# design.net
KiCad netlist of a schematic drawn in EasyEDA
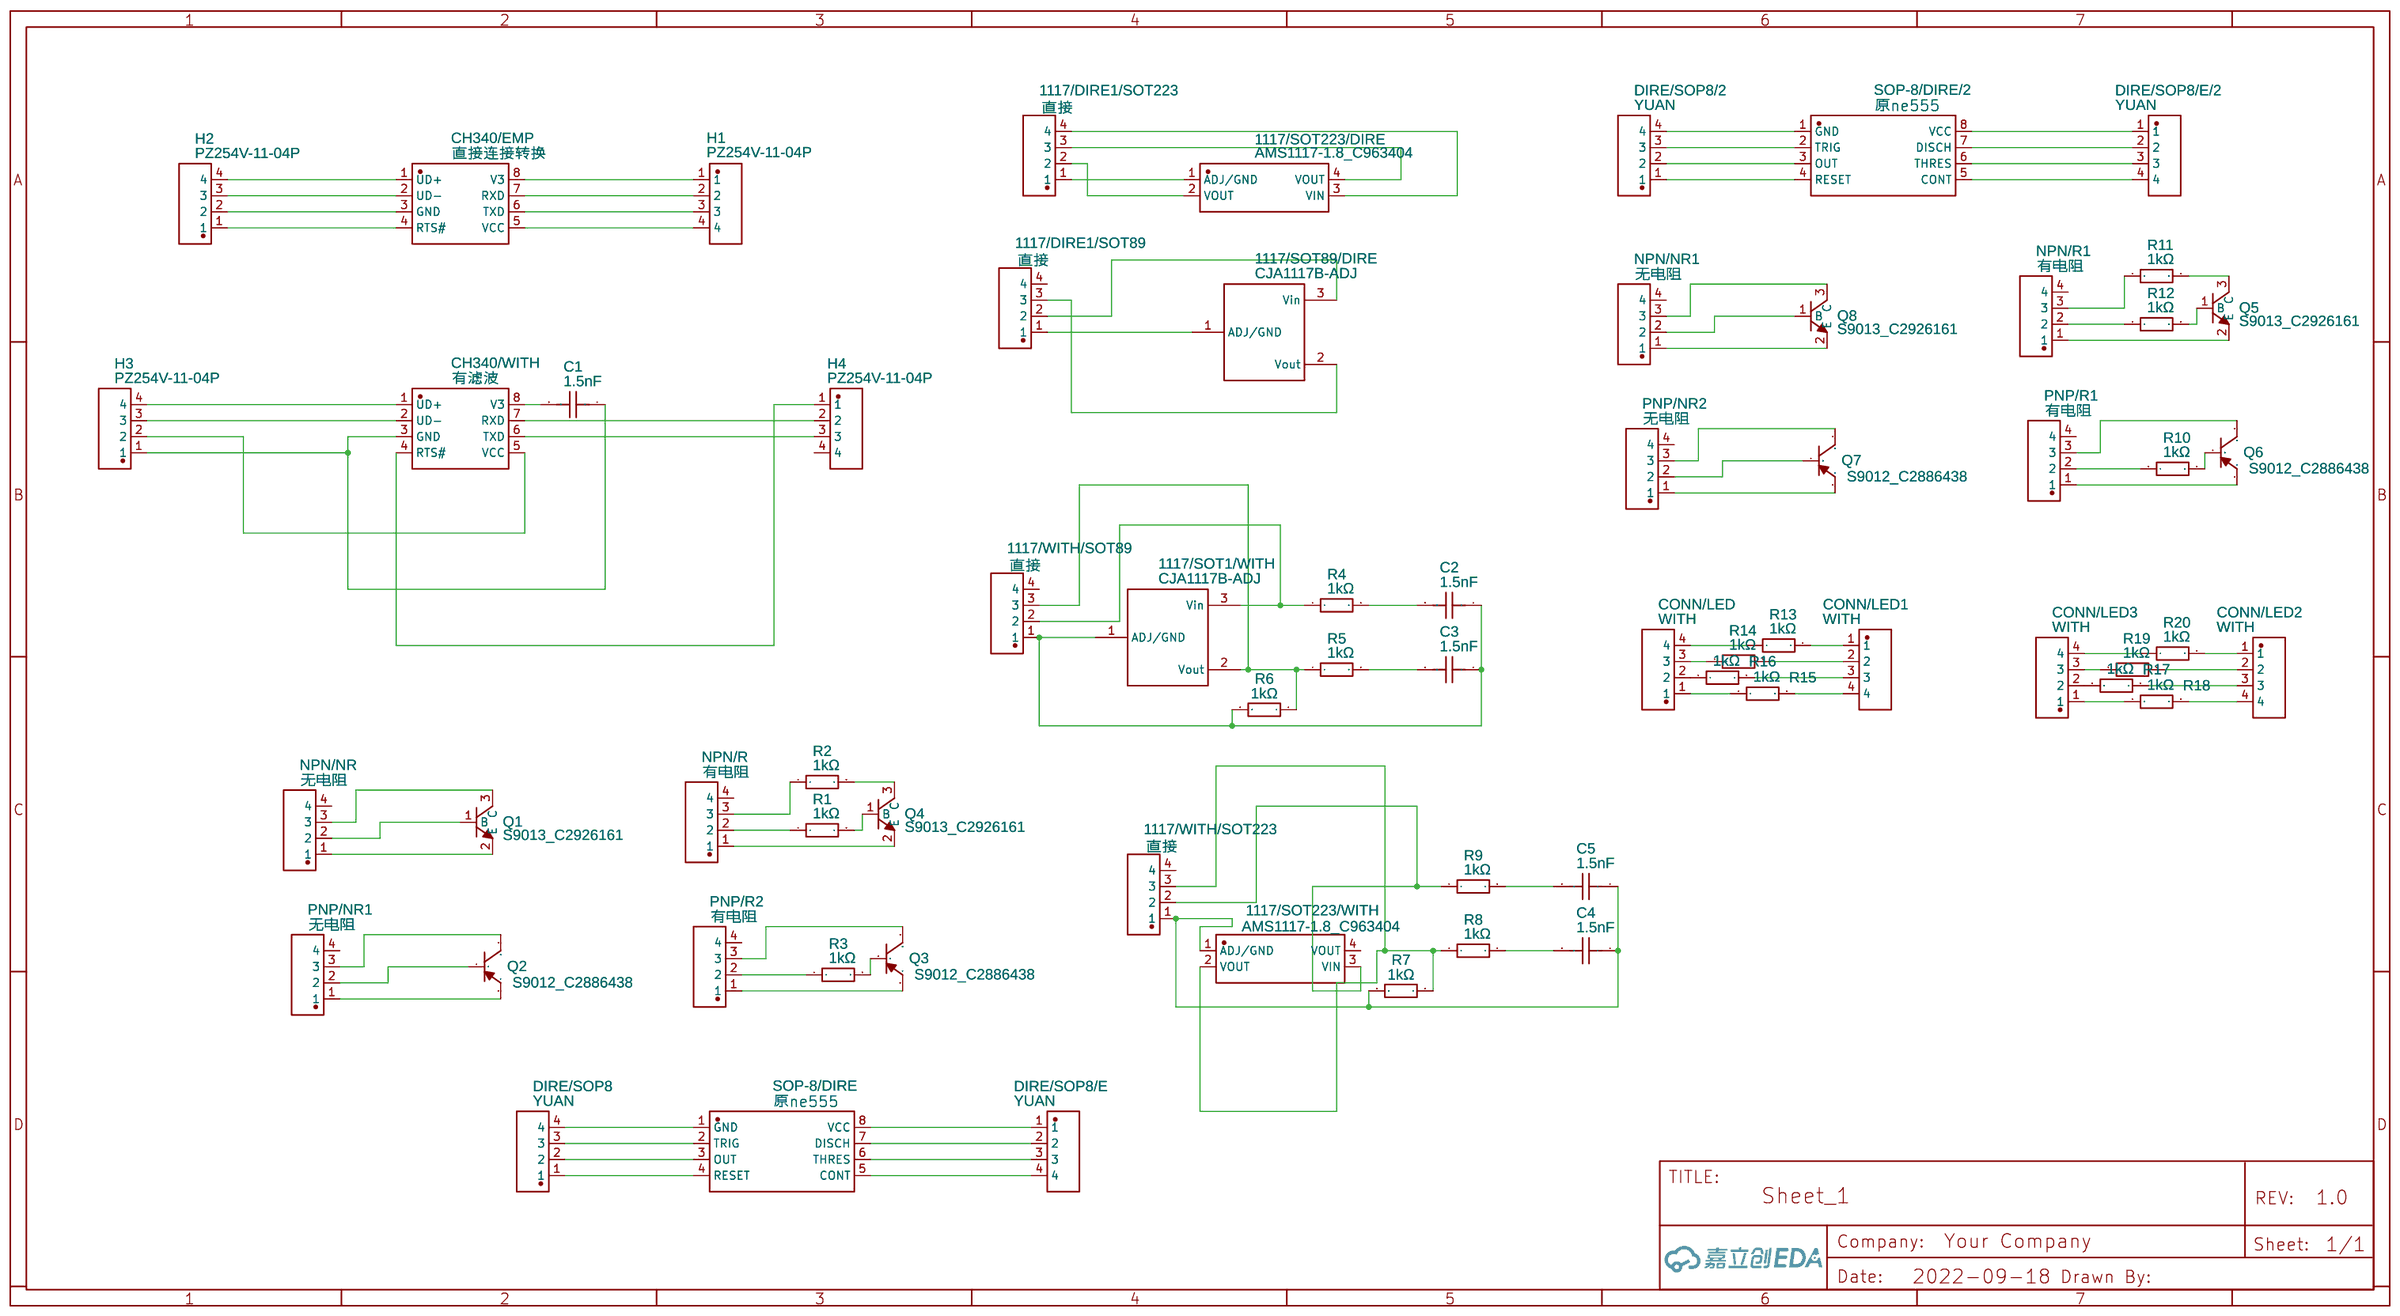
[diagram p0: schematic sheet]

(export (version "E")
  (design (tool "Eeschema 10.0.6"))
  (components
    (comp (ref "1117/DIRE1/SOT89")
      (value "直接")
      (fields
        (field (name "BOM_Manufacturer Part") "PZ254V-11-04P")
        (field (name "BOM_Supplier Part") "C492403")
      )
      (libsource (lib "") (part "PZ254V-11-04P_8"))
    )
    (comp (ref "1117/DIRE1/SOT223")
      (value "直接")
      (fields
        (field (name "BOM_Manufacturer Part") "PZ254V-11-04P")
        (field (name "BOM_Supplier Part") "C492403")
      )
      (libsource (lib "") (part "PZ254V-11-04P_8"))
    )
    (comp (ref "1117/SOT1/WITH")
      (value "CJA1117B-ADJ")
      (fields (field (name "BOM_Supplier Part") "C107222"))
      (libsource (lib "") (part "CJA1117B-ADJ"))
    )
    (comp (ref "1117/SOT89/DIRE")
      (value "CJA1117B-ADJ")
      (fields (field (name "BOM_Supplier Part") "C107222"))
      (libsource (lib "") (part "CJA1117B-ADJ_1"))
    )
    (comp (ref "1117/SOT223/DIRE")
      (value "AMS1117-1.8_C963404")
      (fields
        (field (name "BOM_Manufacturer Part") "AMS1117-1.8")
        (field (name "BOM_Supplier Part") "C963404")
      )
      (libsource (lib "") (part "AMS1117-1.8_C963404"))
    )
    (comp (ref "1117/SOT223/WITH")
      (value "AMS1117-1.8_C963404")
      (fields
        (field (name "BOM_Manufacturer Part") "AMS1117-1.8")
        (field (name "BOM_Supplier Part") "C963404")
      )
      (libsource (lib "") (part "AMS1117-1.8_C963404_1"))
    )
    (comp (ref "1117/WITH/SOT89")
      (value "直接")
      (fields
        (field (name "BOM_Manufacturer Part") "PZ254V-11-04P")
        (field (name "BOM_Supplier Part") "C492403")
      )
      (libsource (lib "") (part "PZ254V-11-04P_9"))
    )
    (comp (ref "1117/WITH/SOT223")
      (value "直接")
      (fields
        (field (name "BOM_Manufacturer Part") "PZ254V-11-04P")
        (field (name "BOM_Supplier Part") "C492403")
      )
      (libsource (lib "") (part "PZ254V-11-04P_9"))
    )
    (comp (ref "C1")
      (value "1.5nF")
      (fields
        (field (name "BOM_Manufacturer Part") "CL10B152KB8NNNC")
        (field (name "BOM_Supplier Part") "C37788")
      )
      (libsource (lib "") (part "CL10B152KB8NNNC"))
    )
    (comp (ref "C2")
      (value "1.5nF")
      (fields
        (field (name "BOM_Manufacturer Part") "CL10B152KB8NNNC")
        (field (name "BOM_Supplier Part") "C37788")
      )
      (libsource (lib "") (part "CL10B152KB8NNNC"))
    )
    (comp (ref "C3")
      (value "1.5nF")
      (fields
        (field (name "BOM_Manufacturer Part") "CL10B152KB8NNNC")
        (field (name "BOM_Supplier Part") "C37788")
      )
      (libsource (lib "") (part "CL10B152KB8NNNC"))
    )
    (comp (ref "C4")
      (value "1.5nF")
      (fields
        (field (name "BOM_Manufacturer Part") "CL10B152KB8NNNC")
        (field (name "BOM_Supplier Part") "C37788")
      )
      (libsource (lib "") (part "CL10B152KB8NNNC"))
    )
    (comp (ref "C5")
      (value "1.5nF")
      (fields
        (field (name "BOM_Manufacturer Part") "CL10B152KB8NNNC")
        (field (name "BOM_Supplier Part") "C37788")
      )
      (libsource (lib "") (part "CL10B152KB8NNNC"))
    )
    (comp (ref "CH340/EMP")
      (value "直接连接转换")
      (fields (field (name "BOM_Manufacturer Part") "CH340N") (field (name "BOM_Supplier Part") "C2977777"))
      (libsource (lib "") (part "CH340N_C2977777"))
    )
    (comp (ref "CH340/WITH")
      (value "有滤波")
      (fields (field (name "BOM_Manufacturer Part") "CH340N") (field (name "BOM_Supplier Part") "C2977777"))
      (libsource (lib "") (part "CH340N_C2977777_1"))
    )
    (comp (ref "CONN/LED")
      (value "WITH")
      (fields
        (field (name "BOM_Manufacturer Part") "PZ254V-11-04P")
        (field (name "BOM_Supplier Part") "C492403")
      )
      (libsource (lib "") (part "PZ254V-11-04P_2"))
    )
    (comp (ref "CONN/LED1")
      (value "WITH")
      (fields
        (field (name "BOM_Manufacturer Part") "PZ254V-11-04P")
        (field (name "BOM_Supplier Part") "C492403")
      )
      (libsource (lib "") (part "PZ254V-11-04P"))
    )
    (comp (ref "CONN/LED2")
      (value "WITH")
      (fields
        (field (name "BOM_Manufacturer Part") "PZ254V-11-04P")
        (field (name "BOM_Supplier Part") "C492403")
      )
      (libsource (lib "") (part "PZ254V-11-04P"))
    )
    (comp (ref "CONN/LED3")
      (value "WITH")
      (fields
        (field (name "BOM_Manufacturer Part") "PZ254V-11-04P")
        (field (name "BOM_Supplier Part") "C492403")
      )
      (libsource (lib "") (part "PZ254V-11-04P_2"))
    )
    (comp (ref "DIRE/SOP8")
      (value "YUAN")
      (fields
        (field (name "BOM_Manufacturer Part") "PZ254V-11-04P")
        (field (name "BOM_Supplier Part") "C492403")
      )
      (libsource (lib "") (part "PZ254V-11-04P_1"))
    )
    (comp (ref "DIRE/SOP8/2")
      (value "YUAN")
      (fields
        (field (name "BOM_Manufacturer Part") "PZ254V-11-04P")
        (field (name "BOM_Supplier Part") "C492403")
      )
      (libsource (lib "") (part "PZ254V-11-04P_4"))
    )
    (comp (ref "DIRE/SOP8/E")
      (value "YUAN")
      (fields
        (field (name "BOM_Manufacturer Part") "PZ254V-11-04P")
        (field (name "BOM_Supplier Part") "C492403")
      )
      (libsource (lib "") (part "PZ254V-11-04P_10"))
    )
    (comp (ref "DIRE/SOP8/E/2")
      (value "YUAN")
      (fields
        (field (name "BOM_Manufacturer Part") "PZ254V-11-04P")
        (field (name "BOM_Supplier Part") "C492403")
      )
      (libsource (lib "") (part "PZ254V-11-04P_13"))
    )
    (comp (ref "H1")
      (value "PZ254V-11-04P")
      (fields (field (name "BOM_Supplier Part") "C492403"))
      (libsource (lib "") (part "PZ254V-11-04P_3"))
    )
    (comp (ref "H2")
      (value "PZ254V-11-04P")
      (fields (field (name "BOM_Supplier Part") "C492403"))
      (libsource (lib "") (part "PZ254V-11-04P_12"))
    )
    (comp (ref "H3")
      (value "PZ254V-11-04P")
      (fields (field (name "BOM_Supplier Part") "C492403"))
      (libsource (lib "") (part "PZ254V-11-04P_12"))
    )
    (comp (ref "H4")
      (value "PZ254V-11-04P")
      (fields (field (name "BOM_Supplier Part") "C492403"))
      (libsource (lib "") (part "PZ254V-11-04P_3"))
    )
    (comp (ref "NPN/NR")
      (value "无电阻")
      (fields
        (field (name "BOM_Manufacturer Part") "PZ254V-11-04P")
        (field (name "BOM_Supplier Part") "C492403")
      )
      (libsource (lib "") (part "PZ254V-11-04P_7"))
    )
    (comp (ref "NPN/NR1")
      (value "无电阻")
      (fields
        (field (name "BOM_Manufacturer Part") "PZ254V-11-04P")
        (field (name "BOM_Supplier Part") "C492403")
      )
      (libsource (lib "") (part "PZ254V-11-04P_7"))
    )
    (comp (ref "NPN/R")
      (value "有电阻")
      (fields
        (field (name "BOM_Manufacturer Part") "PZ254V-11-04P")
        (field (name "BOM_Supplier Part") "C492403")
      )
      (libsource (lib "") (part "PZ254V-11-04P_6"))
    )
    (comp (ref "NPN/R1")
      (value "有电阻")
      (fields
        (field (name "BOM_Manufacturer Part") "PZ254V-11-04P")
        (field (name "BOM_Supplier Part") "C492403")
      )
      (libsource (lib "") (part "PZ254V-11-04P_6"))
    )
    (comp (ref "PNP/NR1")
      (value "无电阻")
      (fields
        (field (name "BOM_Manufacturer Part") "PZ254V-11-04P")
        (field (name "BOM_Supplier Part") "C492403")
      )
      (libsource (lib "") (part "PZ254V-11-04P_5"))
    )
    (comp (ref "PNP/NR2")
      (value "无电阻")
      (fields
        (field (name "BOM_Manufacturer Part") "PZ254V-11-04P")
        (field (name "BOM_Supplier Part") "C492403")
      )
      (libsource (lib "") (part "PZ254V-11-04P_5"))
    )
    (comp (ref "PNP/R1")
      (value "有电阻")
      (fields
        (field (name "BOM_Manufacturer Part") "PZ254V-11-04P")
        (field (name "BOM_Supplier Part") "C492403")
      )
      (libsource (lib "") (part "PZ254V-11-04P_11"))
    )
    (comp (ref "PNP/R2")
      (value "有电阻")
      (fields
        (field (name "BOM_Manufacturer Part") "PZ254V-11-04P")
        (field (name "BOM_Supplier Part") "C492403")
      )
      (libsource (lib "") (part "PZ254V-11-04P_11"))
    )
    (comp (ref "Q1")
      (value "S9013_C2926161")
      (fields (field (name "BOM_Manufacturer Part") "S9013") (field (name "BOM_Supplier Part") "C2926161"))
      (libsource (lib "") (part "S9013_C2926161"))
    )
    (comp (ref "Q2")
      (value "S9012_C2886438")
      (fields (field (name "BOM_Manufacturer Part") "S9012") (field (name "BOM_Supplier Part") "C2886438"))
      (libsource (lib "") (part "S9012_C2886438"))
    )
    (comp (ref "Q3")
      (value "S9012_C2886438")
      (fields (field (name "BOM_Manufacturer Part") "S9012") (field (name "BOM_Supplier Part") "C2886438"))
      (libsource (lib "") (part "S9012_C2886438"))
    )
    (comp (ref "Q4")
      (value "S9013_C2926161")
      (fields (field (name "BOM_Manufacturer Part") "S9013") (field (name "BOM_Supplier Part") "C2926161"))
      (libsource (lib "") (part "S9013_C2926161"))
    )
    (comp (ref "Q5")
      (value "S9013_C2926161")
      (fields (field (name "BOM_Manufacturer Part") "S9013") (field (name "BOM_Supplier Part") "C2926161"))
      (libsource (lib "") (part "S9013_C2926161"))
    )
    (comp (ref "Q6")
      (value "S9012_C2886438")
      (fields (field (name "BOM_Manufacturer Part") "S9012") (field (name "BOM_Supplier Part") "C2886438"))
      (libsource (lib "") (part "S9012_C2886438"))
    )
    (comp (ref "Q7")
      (value "S9012_C2886438")
      (fields (field (name "BOM_Manufacturer Part") "S9012") (field (name "BOM_Supplier Part") "C2886438"))
      (libsource (lib "") (part "S9012_C2886438"))
    )
    (comp (ref "Q8")
      (value "S9013_C2926161")
      (fields (field (name "BOM_Manufacturer Part") "S9013") (field (name "BOM_Supplier Part") "C2926161"))
      (libsource (lib "") (part "S9013_C2926161"))
    )
    (comp (ref "R1")
      (value "1kΩ")
      (fields
        (field (name "BOM_Manufacturer Part") "0603WAF1001T5E")
        (field (name "BOM_Supplier Part") "C21190")
      )
      (libsource (lib "") (part "0603WAF1001T5E"))
    )
    (comp (ref "R2")
      (value "1kΩ")
      (fields
        (field (name "BOM_Manufacturer Part") "0603WAF1001T5E")
        (field (name "BOM_Supplier Part") "C21190")
      )
      (libsource (lib "") (part "0603WAF1001T5E"))
    )
    (comp (ref "R3")
      (value "1kΩ")
      (fields
        (field (name "BOM_Manufacturer Part") "0603WAF1001T5E")
        (field (name "BOM_Supplier Part") "C21190")
      )
      (libsource (lib "") (part "0603WAF1001T5E"))
    )
    (comp (ref "R4")
      (value "1kΩ")
      (fields
        (field (name "BOM_Manufacturer Part") "0603WAF1001T5E")
        (field (name "BOM_Supplier Part") "C21190")
      )
      (libsource (lib "") (part "0603WAF1001T5E"))
    )
    (comp (ref "R5")
      (value "1kΩ")
      (fields
        (field (name "BOM_Manufacturer Part") "0603WAF1001T5E")
        (field (name "BOM_Supplier Part") "C21190")
      )
      (libsource (lib "") (part "0603WAF1001T5E"))
    )
    (comp (ref "R6")
      (value "1kΩ")
      (fields
        (field (name "BOM_Manufacturer Part") "0603WAF1001T5E")
        (field (name "BOM_Supplier Part") "C21190")
      )
      (libsource (lib "") (part "0603WAF1001T5E_1"))
    )
    (comp (ref "R7")
      (value "1kΩ")
      (fields
        (field (name "BOM_Manufacturer Part") "0603WAF1001T5E")
        (field (name "BOM_Supplier Part") "C21190")
      )
      (libsource (lib "") (part "0603WAF1001T5E_1"))
    )
    (comp (ref "R8")
      (value "1kΩ")
      (fields
        (field (name "BOM_Manufacturer Part") "0603WAF1001T5E")
        (field (name "BOM_Supplier Part") "C21190")
      )
      (libsource (lib "") (part "0603WAF1001T5E"))
    )
    (comp (ref "R9")
      (value "1kΩ")
      (fields
        (field (name "BOM_Manufacturer Part") "0603WAF1001T5E")
        (field (name "BOM_Supplier Part") "C21190")
      )
      (libsource (lib "") (part "0603WAF1001T5E"))
    )
    (comp (ref "R10")
      (value "1kΩ")
      (fields
        (field (name "BOM_Manufacturer Part") "0603WAF1001T5E")
        (field (name "BOM_Supplier Part") "C21190")
      )
      (libsource (lib "") (part "0603WAF1001T5E"))
    )
    (comp (ref "R11")
      (value "1kΩ")
      (fields
        (field (name "BOM_Manufacturer Part") "0603WAF1001T5E")
        (field (name "BOM_Supplier Part") "C21190")
      )
      (libsource (lib "") (part "0603WAF1001T5E"))
    )
    (comp (ref "R12")
      (value "1kΩ")
      (fields
        (field (name "BOM_Manufacturer Part") "0603WAF1001T5E")
        (field (name "BOM_Supplier Part") "C21190")
      )
      (libsource (lib "") (part "0603WAF1001T5E"))
    )
    (comp (ref "R13")
      (value "1kΩ")
      (fields
        (field (name "BOM_Manufacturer Part") "0603WAF1001T5E")
        (field (name "BOM_Supplier Part") "C21190")
      )
      (libsource (lib "") (part "0603WAF1001T5E"))
    )
    (comp (ref "R14")
      (value "1kΩ")
      (fields
        (field (name "BOM_Manufacturer Part") "0603WAF1001T5E")
        (field (name "BOM_Supplier Part") "C21190")
      )
      (libsource (lib "") (part "0603WAF1001T5E"))
    )
    (comp (ref "R15")
      (value "1kΩ")
      (fields
        (field (name "BOM_Manufacturer Part") "0603WAF1001T5E")
        (field (name "BOM_Supplier Part") "C21190")
      )
      (libsource (lib "") (part "0603WAF1001T5E"))
    )
    (comp (ref "R16")
      (value "1kΩ")
      (fields
        (field (name "BOM_Manufacturer Part") "0603WAF1001T5E")
        (field (name "BOM_Supplier Part") "C21190")
      )
      (libsource (lib "") (part "0603WAF1001T5E"))
    )
    (comp (ref "R17")
      (value "1kΩ")
      (fields
        (field (name "BOM_Manufacturer Part") "0603WAF1001T5E")
        (field (name "BOM_Supplier Part") "C21190")
      )
      (libsource (lib "") (part "0603WAF1001T5E"))
    )
    (comp (ref "R18")
      (value "1kΩ")
      (fields
        (field (name "BOM_Manufacturer Part") "0603WAF1001T5E")
        (field (name "BOM_Supplier Part") "C21190")
      )
      (libsource (lib "") (part "0603WAF1001T5E"))
    )
    (comp (ref "R19")
      (value "1kΩ")
      (fields
        (field (name "BOM_Manufacturer Part") "0603WAF1001T5E")
        (field (name "BOM_Supplier Part") "C21190")
      )
      (libsource (lib "") (part "0603WAF1001T5E"))
    )
    (comp (ref "R20")
      (value "1kΩ")
      (fields
        (field (name "BOM_Manufacturer Part") "0603WAF1001T5E")
        (field (name "BOM_Supplier Part") "C21190")
      )
      (libsource (lib "") (part "0603WAF1001T5E"))
    )
    (comp (ref "SOP-8/DIRE")
      (value "原ne555")
      (fields (field (name "BOM_Manufacturer Part") "NE555") (field (name "BOM_Supplier Part") "C5125085"))
      (libsource (lib "") (part "NE555_C5125085_1"))
    )
    (comp (ref "SOP-8/DIRE/2")
      (value "原ne555")
      (fields (field (name "BOM_Manufacturer Part") "NE555") (field (name "BOM_Supplier Part") "C5125085"))
      (libsource (lib "") (part "NE555_C5125085"))
    )
  )
  (nets
    (net (code "1") (name "Net-(1117/DIRE1/SOT223-Pad2)") (class "Default")
      (node (ref "1117/DIRE1/SOT223") (pin "2") (pinfunction "2_2") (pintype "unspecified"))
      (node (ref "1117/SOT223/DIRE") (pin "2") (pinfunction "VOUT_2") (pintype "unspecified"))
    )
    (net (code "2") (name "Net-(1117/DIRE1/SOT223-Pad3)") (class "Default")
      (node (ref "1117/DIRE1/SOT223") (pin "3") (pinfunction "3_3") (pintype "unspecified"))
      (node (ref "1117/SOT223/DIRE") (pin "4") (pinfunction "VOUT_4") (pintype "unspecified"))
    )
    (net (code "3") (name "Net-(1117/SOT1/WITH-ADJ{slash}GND)") (class "Default")
      (node (ref "1117/SOT1/WITH") (pin "1") (pinfunction "ADJ/GND_1") (pintype "unspecified"))
      (node (ref "1117/WITH/SOT89") (pin "1") (pinfunction "1_1") (pintype "unspecified"))
      (node (ref "C2") (pin "1") (pinfunction "1_1") (pintype "unspecified"))
      (node (ref "C3") (pin "1") (pinfunction "1_1") (pintype "unspecified"))
      (node (ref "R6") (pin "2") (pinfunction "2_2") (pintype "input"))
    )
    (net (code "4") (name "Net-(1117/SOT1/WITH-Vin)") (class "Default")
      (node (ref "1117/SOT1/WITH") (pin "3") (pinfunction "Vin_3") (pintype "unspecified"))
      (node (ref "1117/WITH/SOT89") (pin "2") (pinfunction "2_2") (pintype "unspecified"))
      (node (ref "R4") (pin "1") (pinfunction "1_1") (pintype "input"))
    )
    (net (code "5") (name "Net-(1117/SOT1/WITH-Vout)") (class "Default")
      (node (ref "1117/SOT1/WITH") (pin "2") (pinfunction "Vout_2") (pintype "unspecified"))
      (node (ref "1117/WITH/SOT89") (pin "3") (pinfunction "3_3") (pintype "unspecified"))
      (node (ref "R5") (pin "1") (pinfunction "1_1") (pintype "input"))
      (node (ref "R6") (pin "1") (pinfunction "1_1") (pintype "input"))
    )
    (net (code "6") (name "Net-(1117/SOT89/DIRE-ADJ{slash}GND)") (class "Default")
      (node (ref "1117/DIRE1/SOT89") (pin "1") (pinfunction "1_1") (pintype "unspecified"))
      (node (ref "1117/SOT89/DIRE") (pin "1") (pinfunction "ADJ/GND_1") (pintype "unspecified"))
    )
    (net (code "7") (name "Net-(1117/SOT89/DIRE-Vin)") (class "Default")
      (node (ref "1117/DIRE1/SOT89") (pin "2") (pinfunction "2_2") (pintype "unspecified"))
      (node (ref "1117/SOT89/DIRE") (pin "3") (pinfunction "Vin_3") (pintype "unspecified"))
    )
    (net (code "8") (name "Net-(1117/SOT89/DIRE-Vout)") (class "Default")
      (node (ref "1117/DIRE1/SOT89") (pin "3") (pinfunction "3_3") (pintype "unspecified"))
      (node (ref "1117/SOT89/DIRE") (pin "2") (pinfunction "Vout_2") (pintype "unspecified"))
    )
    (net (code "9") (name "Net-(1117/SOT223/DIRE-ADJ{slash}GND)") (class "Default")
      (node (ref "1117/DIRE1/SOT223") (pin "1") (pinfunction "1_1") (pintype "unspecified"))
      (node (ref "1117/SOT223/DIRE") (pin "1") (pinfunction "ADJ/GND_1") (pintype "unspecified"))
    )
    (net (code "10") (name "Net-(1117/SOT223/DIRE-VIN)") (class "Default")
      (node (ref "1117/DIRE1/SOT223") (pin "4") (pinfunction "4_4") (pintype "unspecified"))
      (node (ref "1117/SOT223/DIRE") (pin "3") (pinfunction "VIN_3") (pintype "unspecified"))
    )
    (net (code "11") (name "Net-(1117/SOT223/WITH-ADJ{slash}GND)") (class "Default")
      (node (ref "1117/SOT223/WITH") (pin "1") (pinfunction "ADJ/GND_1") (pintype "unspecified"))
      (node (ref "1117/WITH/SOT223") (pin "1") (pinfunction "1_1") (pintype "unspecified"))
      (node (ref "C4") (pin "1") (pinfunction "1_1") (pintype "unspecified"))
      (node (ref "C5") (pin "1") (pinfunction "1_1") (pintype "unspecified"))
      (node (ref "R7") (pin "2") (pinfunction "2_2") (pintype "input"))
    )
    (net (code "12") (name "Net-(1117/SOT223/WITH-VIN)") (class "Default")
      (node (ref "1117/SOT223/WITH") (pin "3") (pinfunction "VIN_3") (pintype "unspecified"))
      (node (ref "1117/WITH/SOT223") (pin "2") (pinfunction "2_2") (pintype "unspecified"))
      (node (ref "R9") (pin "1") (pinfunction "1_1") (pintype "input"))
    )
    (net (code "13") (name "Net-(1117/SOT223/WITH-VOUT-Pad2)") (class "Default")
      (node (ref "1117/SOT223/WITH") (pin "2") (pinfunction "VOUT_2") (pintype "unspecified"))
      (node (ref "1117/WITH/SOT223") (pin "3") (pinfunction "3_3") (pintype "unspecified"))
      (node (ref "R7") (pin "1") (pinfunction "1_1") (pintype "input"))
      (node (ref "R8") (pin "1") (pinfunction "1_1") (pintype "input"))
    )
    (net (code "14") (name "Net-(C2-Pad2)") (class "Default")
      (node (ref "C2") (pin "2") (pinfunction "2_2") (pintype "unspecified"))
      (node (ref "R4") (pin "2") (pinfunction "2_2") (pintype "input"))
    )
    (net (code "15") (name "Net-(C3-Pad2)") (class "Default")
      (node (ref "C3") (pin "2") (pinfunction "2_2") (pintype "unspecified"))
      (node (ref "R5") (pin "2") (pinfunction "2_2") (pintype "input"))
    )
    (net (code "16") (name "Net-(C4-Pad2)") (class "Default")
      (node (ref "C4") (pin "2") (pinfunction "2_2") (pintype "unspecified"))
      (node (ref "R8") (pin "2") (pinfunction "2_2") (pintype "input"))
    )
    (net (code "17") (name "Net-(C5-Pad2)") (class "Default")
      (node (ref "C5") (pin "2") (pinfunction "2_2") (pintype "unspecified"))
      (node (ref "R9") (pin "2") (pinfunction "2_2") (pintype "input"))
    )
    (net (code "18") (name "Net-(CH340/EMP-GND)") (class "Default")
      (node (ref "CH340/EMP") (pin "3") (pinfunction "GND_3") (pintype "unspecified"))
      (node (ref "H2") (pin "2") (pinfunction "2_2") (pintype "unspecified"))
    )
    (net (code "19") (name "Net-(CH340/EMP-RTS#)") (class "Default")
      (node (ref "CH340/EMP") (pin "4") (pinfunction "RTS#_4") (pintype "unspecified"))
      (node (ref "H2") (pin "1") (pinfunction "1_1") (pintype "unspecified"))
    )
    (net (code "20") (name "Net-(CH340/EMP-RXD)") (class "Default")
      (node (ref "CH340/EMP") (pin "7") (pinfunction "RXD_7") (pintype "unspecified"))
      (node (ref "H1") (pin "2") (pinfunction "2_2") (pintype "unspecified"))
    )
    (net (code "21") (name "Net-(CH340/EMP-TXD)") (class "Default")
      (node (ref "CH340/EMP") (pin "6") (pinfunction "TXD_6") (pintype "unspecified"))
      (node (ref "H1") (pin "3") (pinfunction "3_3") (pintype "unspecified"))
    )
    (net (code "22") (name "Net-(CH340/EMP-UD+)") (class "Default")
      (node (ref "CH340/EMP") (pin "1") (pinfunction "UD+_1") (pintype "unspecified"))
      (node (ref "H2") (pin "4") (pinfunction "4_4") (pintype "unspecified"))
    )
    (net (code "23") (name "Net-(CH340/EMP-UD-)") (class "Default")
      (node (ref "CH340/EMP") (pin "2") (pinfunction "UD-_2") (pintype "unspecified"))
      (node (ref "H2") (pin "3") (pinfunction "3_3") (pintype "unspecified"))
    )
    (net (code "24") (name "Net-(CH340/EMP-V3)") (class "Default")
      (node (ref "CH340/EMP") (pin "8") (pinfunction "V3_8") (pintype "unspecified"))
      (node (ref "H1") (pin "1") (pinfunction "1_1") (pintype "unspecified"))
    )
    (net (code "25") (name "Net-(CH340/EMP-VCC)") (class "Default")
      (node (ref "CH340/EMP") (pin "5") (pinfunction "VCC_5") (pintype "unspecified"))
      (node (ref "H1") (pin "4") (pinfunction "4_4") (pintype "unspecified"))
    )
    (net (code "26") (name "Net-(CH340/WITH-GND)") (class "Default")
      (node (ref "C1") (pin "1") (pinfunction "1_1") (pintype "unspecified"))
      (node (ref "CH340/WITH") (pin "3") (pinfunction "GND_3") (pintype "unspecified"))
      (node (ref "H3") (pin "1") (pinfunction "1_1") (pintype "unspecified"))
    )
    (net (code "27") (name "Net-(CH340/WITH-RTS#)") (class "Default")
      (node (ref "CH340/WITH") (pin "4") (pinfunction "RTS#_4") (pintype "unspecified"))
      (node (ref "H4") (pin "1") (pinfunction "1_1") (pintype "unspecified"))
    )
    (net (code "28") (name "Net-(CH340/WITH-RXD)") (class "Default")
      (node (ref "CH340/WITH") (pin "7") (pinfunction "RXD_7") (pintype "unspecified"))
      (node (ref "H4") (pin "2") (pinfunction "2_2") (pintype "unspecified"))
    )
    (net (code "29") (name "Net-(CH340/WITH-TXD)") (class "Default")
      (node (ref "CH340/WITH") (pin "6") (pinfunction "TXD_6") (pintype "unspecified"))
      (node (ref "H4") (pin "3") (pinfunction "3_3") (pintype "unspecified"))
    )
    (net (code "30") (name "Net-(CH340/WITH-UD+)") (class "Default")
      (node (ref "CH340/WITH") (pin "1") (pinfunction "UD+_1") (pintype "unspecified"))
      (node (ref "H3") (pin "4") (pinfunction "4_4") (pintype "unspecified"))
    )
    (net (code "31") (name "Net-(CH340/WITH-UD-)") (class "Default")
      (node (ref "CH340/WITH") (pin "2") (pinfunction "UD-_2") (pintype "unspecified"))
      (node (ref "H3") (pin "3") (pinfunction "3_3") (pintype "unspecified"))
    )
    (net (code "32") (name "Net-(CH340/WITH-V3)") (class "Default")
      (node (ref "C1") (pin "2") (pinfunction "2_2") (pintype "unspecified"))
      (node (ref "CH340/WITH") (pin "8") (pinfunction "V3_8") (pintype "unspecified"))
    )
    (net (code "33") (name "Net-(CH340/WITH-VCC)") (class "Default")
      (node (ref "CH340/WITH") (pin "5") (pinfunction "VCC_5") (pintype "unspecified"))
      (node (ref "H3") (pin "2") (pinfunction "2_2") (pintype "unspecified"))
    )
    (net (code "34") (name "Net-(CONN/LED-Pad1)") (class "Default")
      (node (ref "CONN/LED") (pin "1") (pinfunction "1_1") (pintype "unspecified"))
      (node (ref "R15") (pin "1") (pinfunction "1_1") (pintype "input"))
    )
    (net (code "35") (name "Net-(CONN/LED-Pad2)") (class "Default")
      (node (ref "CONN/LED") (pin "2") (pinfunction "2_2") (pintype "unspecified"))
      (node (ref "R16") (pin "1") (pinfunction "1_1") (pintype "input"))
    )
    (net (code "36") (name "Net-(CONN/LED-Pad3)") (class "Default")
      (node (ref "CONN/LED") (pin "3") (pinfunction "3_3") (pintype "unspecified"))
      (node (ref "R14") (pin "1") (pinfunction "1_1") (pintype "input"))
    )
    (net (code "37") (name "Net-(CONN/LED-Pad4)") (class "Default")
      (node (ref "CONN/LED") (pin "4") (pinfunction "4_4") (pintype "unspecified"))
      (node (ref "R13") (pin "1") (pinfunction "1_1") (pintype "input"))
    )
    (net (code "38") (name "Net-(CONN/LED1-Pad1)") (class "Default")
      (node (ref "CONN/LED1") (pin "1") (pinfunction "1_1") (pintype "unspecified"))
      (node (ref "R13") (pin "2") (pinfunction "2_2") (pintype "input"))
    )
    (net (code "39") (name "Net-(CONN/LED1-Pad2)") (class "Default")
      (node (ref "CONN/LED1") (pin "2") (pinfunction "2_2") (pintype "unspecified"))
      (node (ref "R14") (pin "2") (pinfunction "2_2") (pintype "input"))
    )
    (net (code "40") (name "Net-(CONN/LED1-Pad3)") (class "Default")
      (node (ref "CONN/LED1") (pin "3") (pinfunction "3_3") (pintype "unspecified"))
      (node (ref "R16") (pin "2") (pinfunction "2_2") (pintype "input"))
    )
    (net (code "41") (name "Net-(CONN/LED1-Pad4)") (class "Default")
      (node (ref "CONN/LED1") (pin "4") (pinfunction "4_4") (pintype "unspecified"))
      (node (ref "R15") (pin "2") (pinfunction "2_2") (pintype "input"))
    )
    (net (code "42") (name "Net-(CONN/LED2-Pad1)") (class "Default")
      (node (ref "CONN/LED2") (pin "1") (pinfunction "1_1") (pintype "unspecified"))
      (node (ref "R20") (pin "2") (pinfunction "2_2") (pintype "input"))
    )
    (net (code "43") (name "Net-(CONN/LED2-Pad2)") (class "Default")
      (node (ref "CONN/LED2") (pin "2") (pinfunction "2_2") (pintype "unspecified"))
      (node (ref "R19") (pin "2") (pinfunction "2_2") (pintype "input"))
    )
    (net (code "44") (name "Net-(CONN/LED2-Pad3)") (class "Default")
      (node (ref "CONN/LED2") (pin "3") (pinfunction "3_3") (pintype "unspecified"))
      (node (ref "R17") (pin "2") (pinfunction "2_2") (pintype "input"))
    )
    (net (code "45") (name "Net-(CONN/LED2-Pad4)") (class "Default")
      (node (ref "CONN/LED2") (pin "4") (pinfunction "4_4") (pintype "unspecified"))
      (node (ref "R18") (pin "2") (pinfunction "2_2") (pintype "input"))
    )
    (net (code "46") (name "Net-(CONN/LED3-Pad1)") (class "Default")
      (node (ref "CONN/LED3") (pin "1") (pinfunction "1_1") (pintype "unspecified"))
      (node (ref "R18") (pin "1") (pinfunction "1_1") (pintype "input"))
    )
    (net (code "47") (name "Net-(CONN/LED3-Pad2)") (class "Default")
      (node (ref "CONN/LED3") (pin "2") (pinfunction "2_2") (pintype "unspecified"))
      (node (ref "R17") (pin "1") (pinfunction "1_1") (pintype "input"))
    )
    (net (code "48") (name "Net-(CONN/LED3-Pad3)") (class "Default")
      (node (ref "CONN/LED3") (pin "3") (pinfunction "3_3") (pintype "unspecified"))
      (node (ref "R19") (pin "1") (pinfunction "1_1") (pintype "input"))
    )
    (net (code "49") (name "Net-(CONN/LED3-Pad4)") (class "Default")
      (node (ref "CONN/LED3") (pin "4") (pinfunction "4_4") (pintype "unspecified"))
      (node (ref "R20") (pin "1") (pinfunction "1_1") (pintype "input"))
    )
    (net (code "50") (name "Net-(NPN/R-Pad2)") (class "Default")
      (node (ref "NPN/R") (pin "2") (pinfunction "2_2") (pintype "unspecified"))
      (node (ref "R1") (pin "1") (pinfunction "1_1") (pintype "input"))
    )
    (net (code "51") (name "Net-(NPN/R-Pad3)") (class "Default")
      (node (ref "NPN/R") (pin "3") (pinfunction "3_3") (pintype "unspecified"))
      (node (ref "R2") (pin "1") (pinfunction "1_1") (pintype "input"))
    )
    (net (code "52") (name "Net-(NPN/R1-Pad2)") (class "Default")
      (node (ref "NPN/R1") (pin "2") (pinfunction "2_2") (pintype "unspecified"))
      (node (ref "R12") (pin "1") (pinfunction "1_1") (pintype "input"))
    )
    (net (code "53") (name "Net-(NPN/R1-Pad3)") (class "Default")
      (node (ref "NPN/R1") (pin "3") (pinfunction "3_3") (pintype "unspecified"))
      (node (ref "R11") (pin "1") (pinfunction "1_1") (pintype "input"))
    )
    (net (code "54") (name "Net-(PNP/R1-Pad2)") (class "Default")
      (node (ref "PNP/R1") (pin "2") (pinfunction "2_2") (pintype "unspecified"))
      (node (ref "R10") (pin "1") (pinfunction "1_1") (pintype "input"))
    )
    (net (code "55") (name "Net-(PNP/R2-Pad2)") (class "Default")
      (node (ref "PNP/R2") (pin "2") (pinfunction "2_2") (pintype "unspecified"))
      (node (ref "R3") (pin "1") (pinfunction "1_1") (pintype "input"))
    )
    (net (code "56") (name "Net-(Q1-B)") (class "Default")
      (node (ref "NPN/NR") (pin "2") (pinfunction "2_2") (pintype "unspecified"))
      (node (ref "Q1") (pin "1") (pinfunction "B_1") (pintype "input"))
    )
    (net (code "57") (name "Net-(Q1-C)") (class "Default")
      (node (ref "NPN/NR") (pin "3") (pinfunction "3_3") (pintype "unspecified"))
      (node (ref "Q1") (pin "3") (pinfunction "C_3") (pintype "input"))
    )
    (net (code "58") (name "Net-(Q1-E)") (class "Default")
      (node (ref "NPN/NR") (pin "1") (pinfunction "1_1") (pintype "unspecified"))
      (node (ref "Q1") (pin "2") (pinfunction "E_2") (pintype "input"))
    )
    (net (code "59") (name "Net-(Q2-B)") (class "Default")
      (node (ref "PNP/NR1") (pin "2") (pinfunction "2_2") (pintype "unspecified"))
      (node (ref "Q2") (pin "1") (pinfunction "B_1") (pintype "input"))
    )
    (net (code "60") (name "Net-(Q2-C)") (class "Default")
      (node (ref "PNP/NR1") (pin "3") (pinfunction "3_3") (pintype "unspecified"))
      (node (ref "Q2") (pin "3") (pinfunction "C_3") (pintype "input"))
    )
    (net (code "61") (name "Net-(Q2-E)") (class "Default")
      (node (ref "PNP/NR1") (pin "1") (pinfunction "1_1") (pintype "unspecified"))
      (node (ref "Q2") (pin "2") (pinfunction "E_2") (pintype "input"))
    )
    (net (code "62") (name "Net-(Q3-B)") (class "Default")
      (node (ref "Q3") (pin "1") (pinfunction "B_1") (pintype "input"))
      (node (ref "R3") (pin "2") (pinfunction "2_2") (pintype "input"))
    )
    (net (code "63") (name "Net-(Q3-C)") (class "Default")
      (node (ref "PNP/R2") (pin "3") (pinfunction "3_3") (pintype "unspecified"))
      (node (ref "Q3") (pin "3") (pinfunction "C_3") (pintype "input"))
    )
    (net (code "64") (name "Net-(Q3-E)") (class "Default")
      (node (ref "PNP/R2") (pin "1") (pinfunction "1_1") (pintype "unspecified"))
      (node (ref "Q3") (pin "2") (pinfunction "E_2") (pintype "input"))
    )
    (net (code "65") (name "Net-(Q4-B)") (class "Default")
      (node (ref "Q4") (pin "1") (pinfunction "B_1") (pintype "input"))
      (node (ref "R1") (pin "2") (pinfunction "2_2") (pintype "input"))
    )
    (net (code "66") (name "Net-(Q4-C)") (class "Default")
      (node (ref "Q4") (pin "3") (pinfunction "C_3") (pintype "input"))
      (node (ref "R2") (pin "2") (pinfunction "2_2") (pintype "input"))
    )
    (net (code "67") (name "Net-(Q4-E)") (class "Default")
      (node (ref "NPN/R") (pin "1") (pinfunction "1_1") (pintype "unspecified"))
      (node (ref "Q4") (pin "2") (pinfunction "E_2") (pintype "input"))
    )
    (net (code "68") (name "Net-(Q5-B)") (class "Default")
      (node (ref "Q5") (pin "1") (pinfunction "B_1") (pintype "input"))
      (node (ref "R12") (pin "2") (pinfunction "2_2") (pintype "input"))
    )
    (net (code "69") (name "Net-(Q5-C)") (class "Default")
      (node (ref "Q5") (pin "3") (pinfunction "C_3") (pintype "input"))
      (node (ref "R11") (pin "2") (pinfunction "2_2") (pintype "input"))
    )
    (net (code "70") (name "Net-(Q5-E)") (class "Default")
      (node (ref "NPN/R1") (pin "1") (pinfunction "1_1") (pintype "unspecified"))
      (node (ref "Q5") (pin "2") (pinfunction "E_2") (pintype "input"))
    )
    (net (code "71") (name "Net-(Q6-B)") (class "Default")
      (node (ref "Q6") (pin "1") (pinfunction "B_1") (pintype "input"))
      (node (ref "R10") (pin "2") (pinfunction "2_2") (pintype "input"))
    )
    (net (code "72") (name "Net-(Q6-C)") (class "Default")
      (node (ref "PNP/R1") (pin "3") (pinfunction "3_3") (pintype "unspecified"))
      (node (ref "Q6") (pin "3") (pinfunction "C_3") (pintype "input"))
    )
    (net (code "73") (name "Net-(Q6-E)") (class "Default")
      (node (ref "PNP/R1") (pin "1") (pinfunction "1_1") (pintype "unspecified"))
      (node (ref "Q6") (pin "2") (pinfunction "E_2") (pintype "input"))
    )
    (net (code "74") (name "Net-(Q7-B)") (class "Default")
      (node (ref "PNP/NR2") (pin "2") (pinfunction "2_2") (pintype "unspecified"))
      (node (ref "Q7") (pin "1") (pinfunction "B_1") (pintype "input"))
    )
    (net (code "75") (name "Net-(Q7-C)") (class "Default")
      (node (ref "PNP/NR2") (pin "3") (pinfunction "3_3") (pintype "unspecified"))
      (node (ref "Q7") (pin "3") (pinfunction "C_3") (pintype "input"))
    )
    (net (code "76") (name "Net-(Q7-E)") (class "Default")
      (node (ref "PNP/NR2") (pin "1") (pinfunction "1_1") (pintype "unspecified"))
      (node (ref "Q7") (pin "2") (pinfunction "E_2") (pintype "input"))
    )
    (net (code "77") (name "Net-(Q8-B)") (class "Default")
      (node (ref "NPN/NR1") (pin "2") (pinfunction "2_2") (pintype "unspecified"))
      (node (ref "Q8") (pin "1") (pinfunction "B_1") (pintype "input"))
    )
    (net (code "78") (name "Net-(Q8-C)") (class "Default")
      (node (ref "NPN/NR1") (pin "3") (pinfunction "3_3") (pintype "unspecified"))
      (node (ref "Q8") (pin "3") (pinfunction "C_3") (pintype "input"))
    )
    (net (code "79") (name "Net-(Q8-E)") (class "Default")
      (node (ref "NPN/NR1") (pin "1") (pinfunction "1_1") (pintype "unspecified"))
      (node (ref "Q8") (pin "2") (pinfunction "E_2") (pintype "input"))
    )
    (net (code "80") (name "Net-(SOP-8/DIRE-CONT)") (class "Default")
      (node (ref "DIRE/SOP8/E") (pin "4") (pinfunction "4_4") (pintype "unspecified"))
      (node (ref "SOP-8/DIRE") (pin "5") (pinfunction "CONT_5") (pintype "unspecified"))
    )
    (net (code "81") (name "Net-(SOP-8/DIRE-DISCH)") (class "Default")
      (node (ref "DIRE/SOP8/E") (pin "2") (pinfunction "2_2") (pintype "unspecified"))
      (node (ref "SOP-8/DIRE") (pin "7") (pinfunction "DISCH_7") (pintype "unspecified"))
    )
    (net (code "82") (name "Net-(SOP-8/DIRE-GND)") (class "Default")
      (node (ref "DIRE/SOP8") (pin "4") (pinfunction "4_4") (pintype "unspecified"))
      (node (ref "SOP-8/DIRE") (pin "1") (pinfunction "GND_1") (pintype "unspecified"))
    )
    (net (code "83") (name "Net-(SOP-8/DIRE-OUT)") (class "Default")
      (node (ref "DIRE/SOP8") (pin "2") (pinfunction "2_2") (pintype "unspecified"))
      (node (ref "SOP-8/DIRE") (pin "3") (pinfunction "OUT_3") (pintype "unspecified"))
    )
    (net (code "84") (name "Net-(SOP-8/DIRE-RESET)") (class "Default")
      (node (ref "DIRE/SOP8") (pin "1") (pinfunction "1_1") (pintype "unspecified"))
      (node (ref "SOP-8/DIRE") (pin "4") (pinfunction "RESET_4") (pintype "unspecified"))
    )
    (net (code "85") (name "Net-(SOP-8/DIRE-THRES)") (class "Default")
      (node (ref "DIRE/SOP8/E") (pin "3") (pinfunction "3_3") (pintype "unspecified"))
      (node (ref "SOP-8/DIRE") (pin "6") (pinfunction "THRES_6") (pintype "unspecified"))
    )
    (net (code "86") (name "Net-(SOP-8/DIRE-TRIG)") (class "Default")
      (node (ref "DIRE/SOP8") (pin "3") (pinfunction "3_3") (pintype "unspecified"))
      (node (ref "SOP-8/DIRE") (pin "2") (pinfunction "TRIG_2") (pintype "unspecified"))
    )
    (net (code "87") (name "Net-(SOP-8/DIRE-VCC)") (class "Default")
      (node (ref "DIRE/SOP8/E") (pin "1") (pinfunction "1_1") (pintype "unspecified"))
      (node (ref "SOP-8/DIRE") (pin "8") (pinfunction "VCC_8") (pintype "unspecified"))
    )
    (net (code "88") (name "Net-(SOP-8/DIRE/2-CONT)") (class "Default")
      (node (ref "DIRE/SOP8/E/2") (pin "4") (pinfunction "4_4") (pintype "unspecified"))
      (node (ref "SOP-8/DIRE/2") (pin "5") (pinfunction "CONT_5") (pintype "unspecified"))
    )
    (net (code "89") (name "Net-(SOP-8/DIRE/2-DISCH)") (class "Default")
      (node (ref "DIRE/SOP8/E/2") (pin "2") (pinfunction "2_2") (pintype "unspecified"))
      (node (ref "SOP-8/DIRE/2") (pin "7") (pinfunction "DISCH_7") (pintype "unspecified"))
    )
    (net (code "90") (name "Net-(SOP-8/DIRE/2-GND)") (class "Default")
      (node (ref "DIRE/SOP8/2") (pin "4") (pinfunction "4_4") (pintype "unspecified"))
      (node (ref "SOP-8/DIRE/2") (pin "1") (pinfunction "GND_1") (pintype "unspecified"))
    )
    (net (code "91") (name "Net-(SOP-8/DIRE/2-OUT)") (class "Default")
      (node (ref "DIRE/SOP8/2") (pin "2") (pinfunction "2_2") (pintype "unspecified"))
      (node (ref "SOP-8/DIRE/2") (pin "3") (pinfunction "OUT_3") (pintype "unspecified"))
    )
    (net (code "92") (name "Net-(SOP-8/DIRE/2-RESET)") (class "Default")
      (node (ref "DIRE/SOP8/2") (pin "1") (pinfunction "1_1") (pintype "unspecified"))
      (node (ref "SOP-8/DIRE/2") (pin "4") (pinfunction "RESET_4") (pintype "unspecified"))
    )
    (net (code "93") (name "Net-(SOP-8/DIRE/2-THRES)") (class "Default")
      (node (ref "DIRE/SOP8/E/2") (pin "3") (pinfunction "3_3") (pintype "unspecified"))
      (node (ref "SOP-8/DIRE/2") (pin "6") (pinfunction "THRES_6") (pintype "unspecified"))
    )
    (net (code "94") (name "Net-(SOP-8/DIRE/2-TRIG)") (class "Default")
      (node (ref "DIRE/SOP8/2") (pin "3") (pinfunction "3_3") (pintype "unspecified"))
      (node (ref "SOP-8/DIRE/2") (pin "2") (pinfunction "TRIG_2") (pintype "unspecified"))
    )
    (net (code "95") (name "Net-(SOP-8/DIRE/2-VCC)") (class "Default")
      (node (ref "DIRE/SOP8/E/2") (pin "1") (pinfunction "1_1") (pintype "unspecified"))
      (node (ref "SOP-8/DIRE/2") (pin "8") (pinfunction "VCC_8") (pintype "unspecified"))
    )
    (net (code "96") (name "unconnected-(1117/DIRE1/SOT89-Pad4)") (class "Default")
      (node (ref "1117/DIRE1/SOT89") (pin "4") (pinfunction "4_4") (pintype "unspecified"))
    )
    (net (code "97") (name "unconnected-(1117/SOT223/WITH-VOUT-Pad4)") (class "Default")
      (node (ref "1117/SOT223/WITH") (pin "4") (pinfunction "VOUT_4") (pintype "unspecified"))
    )
    (net (code "98") (name "unconnected-(1117/WITH/SOT89-Pad4)") (class "Default")
      (node (ref "1117/WITH/SOT89") (pin "4") (pinfunction "4_4") (pintype "unspecified"))
    )
    (net (code "99") (name "unconnected-(1117/WITH/SOT223-Pad4)") (class "Default")
      (node (ref "1117/WITH/SOT223") (pin "4") (pinfunction "4_4") (pintype "unspecified"))
    )
    (net (code "100") (name "unconnected-(H4-Pad4)") (class "Default")
      (node (ref "H4") (pin "4") (pinfunction "4_4") (pintype "unspecified"))
    )
    (net (code "101") (name "unconnected-(NPN/NR-Pad4)") (class "Default")
      (node (ref "NPN/NR") (pin "4") (pinfunction "4_4") (pintype "unspecified"))
    )
    (net (code "102") (name "unconnected-(NPN/NR1-Pad4)") (class "Default")
      (node (ref "NPN/NR1") (pin "4") (pinfunction "4_4") (pintype "unspecified"))
    )
    (net (code "103") (name "unconnected-(NPN/R-Pad4)") (class "Default")
      (node (ref "NPN/R") (pin "4") (pinfunction "4_4") (pintype "unspecified"))
    )
    (net (code "104") (name "unconnected-(NPN/R1-Pad4)") (class "Default")
      (node (ref "NPN/R1") (pin "4") (pinfunction "4_4") (pintype "unspecified"))
    )
    (net (code "105") (name "unconnected-(PNP/NR1-Pad4)") (class "Default")
      (node (ref "PNP/NR1") (pin "4") (pinfunction "4_4") (pintype "unspecified"))
    )
    (net (code "106") (name "unconnected-(PNP/NR2-Pad4)") (class "Default")
      (node (ref "PNP/NR2") (pin "4") (pinfunction "4_4") (pintype "unspecified"))
    )
    (net (code "107") (name "unconnected-(PNP/R1-Pad4)") (class "Default")
      (node (ref "PNP/R1") (pin "4") (pinfunction "4_4") (pintype "unspecified"))
    )
    (net (code "108") (name "unconnected-(PNP/R2-Pad4)") (class "Default")
      (node (ref "PNP/R2") (pin "4") (pinfunction "4_4") (pintype "unspecified"))
    )
  )
)
